# PIC32_BREAKOUT.net
KiCad netlist of a schematic drawn in EAGLE
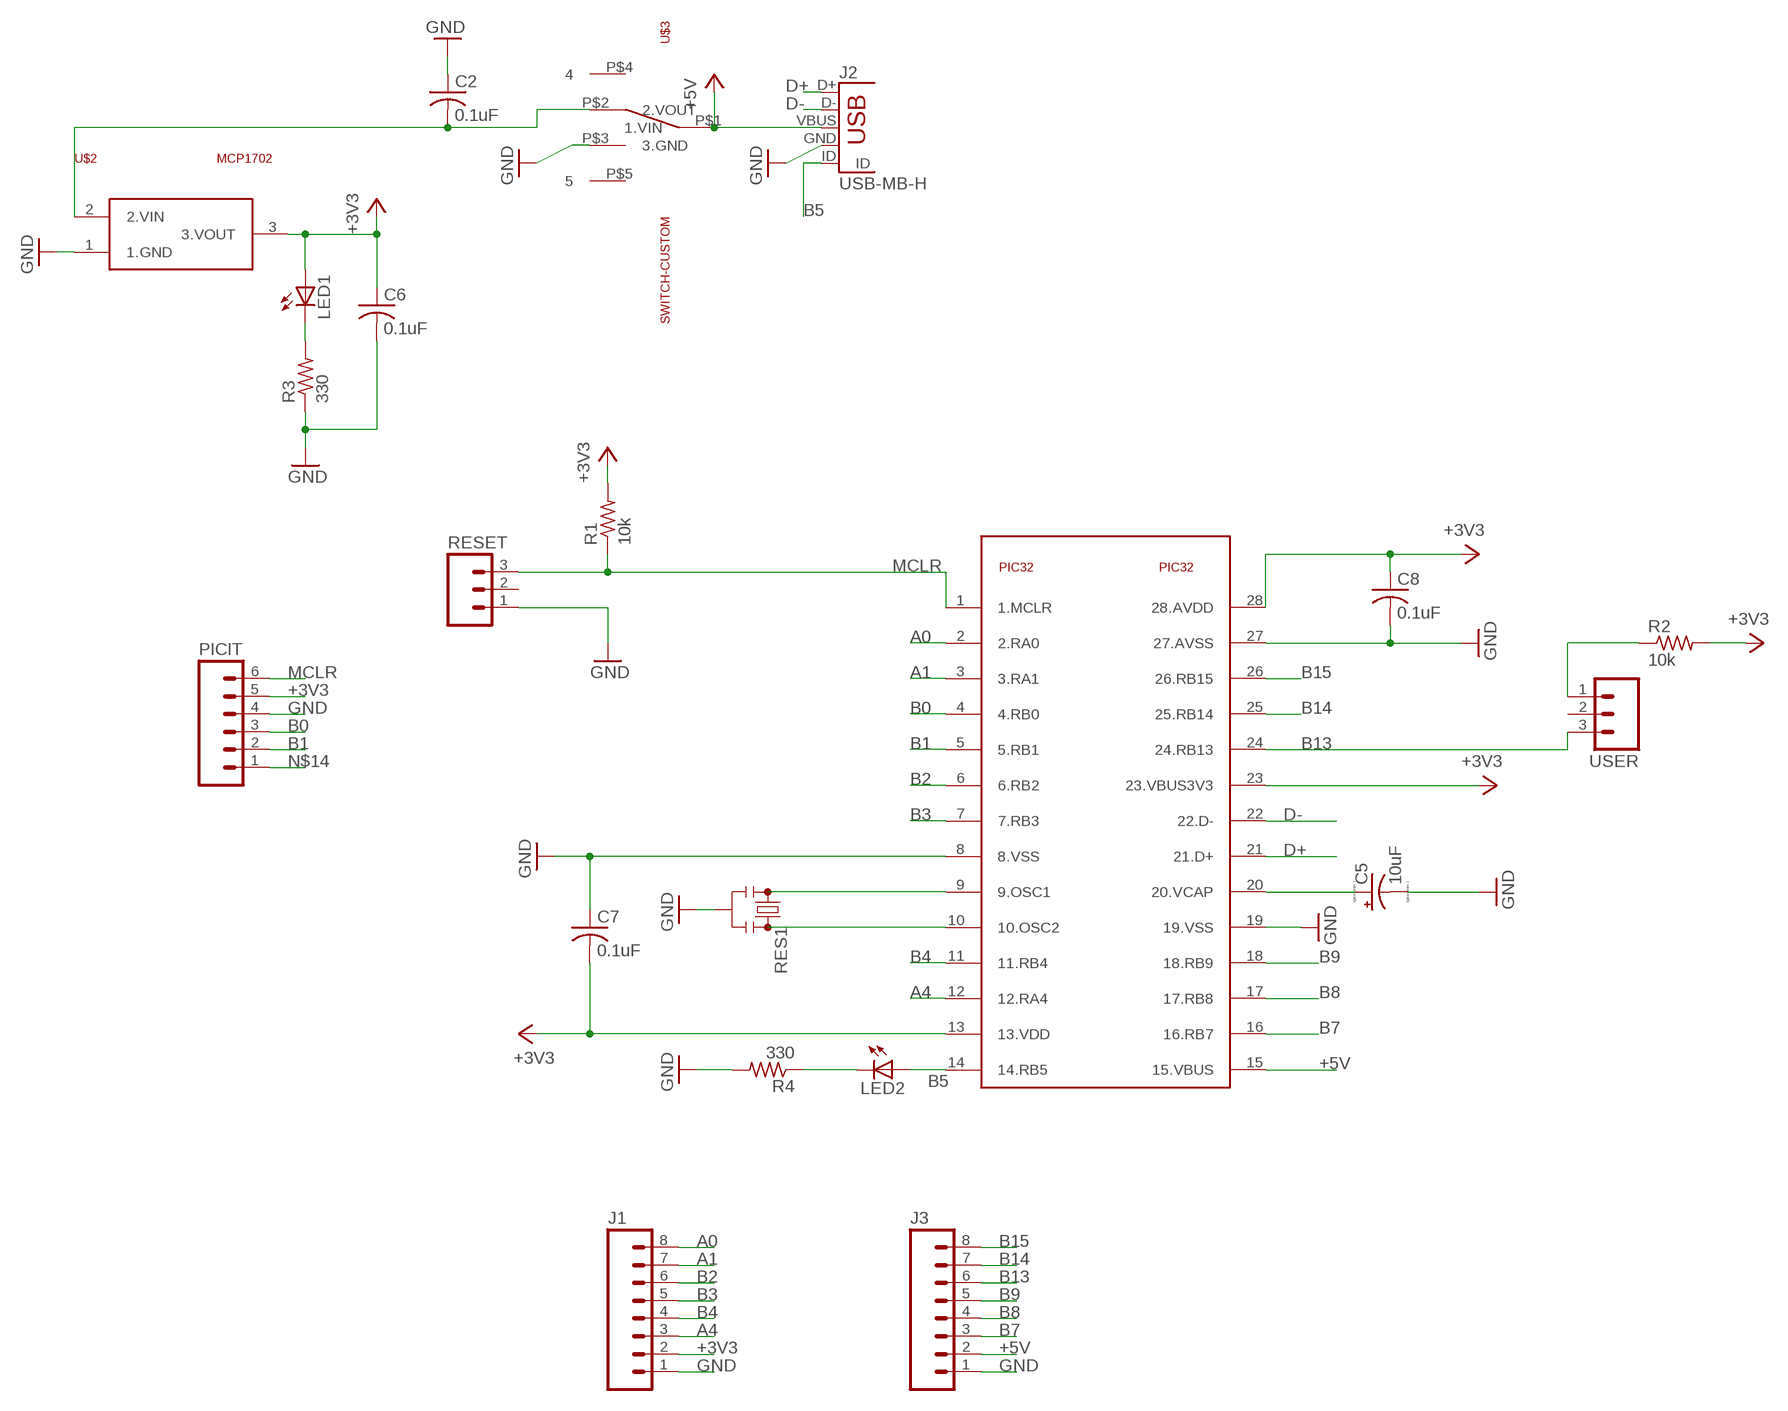
[diagram p0: schematic, sheet 1]

(export (version "E")
  (design (tool "Eeschema 10.0.6"))
  (components
    (comp (ref "C2")
      (value "0.1uF")
      (footprint "eagle-import:C025-024X044")
      (libsource (lib "eagle-import") (part "C-US025-024X044"))
    )
    (comp (ref "C5")
      (value "10uF")
      (footprint "eagle-import:B45181A")
      (libsource (lib "eagle-import") (part "CPOL-USB45181A"))
    )
    (comp (ref "C6")
      (value "0.1uF")
      (footprint "eagle-import:C025-024X044")
      (libsource (lib "eagle-import") (part "C-US025-024X044"))
    )
    (comp (ref "C7")
      (value "0.1uF")
      (footprint "eagle-import:C025-024X044")
      (libsource (lib "eagle-import") (part "C-US025-024X044"))
    )
    (comp (ref "C8")
      (value "0.1uF")
      (footprint "eagle-import:C025-024X044")
      (libsource (lib "eagle-import") (part "C-US025-024X044"))
    )
    (comp (ref "J1")
      (value "M08")
      (footprint "eagle-import:1X08_ROUND")
      (libsource (lib "eagle-import") (part "M08"))
    )
    (comp (ref "J2")
      (value "USB-MB-H")
      (footprint "eagle-import:USB-MB-H")
      (libsource (lib "eagle-import") (part "USB-MB-H"))
    )
    (comp (ref "J3")
      (value "M08")
      (footprint "eagle-import:1X08_ROUND")
      (libsource (lib "eagle-import") (part "M08"))
    )
    (comp (ref "LED1")
      (value "LED3MM")
      (footprint "eagle-import:LED3MM")
      (libsource (lib "eagle-import") (part "LED3MM"))
    )
    (comp (ref "LED2")
      (value "LED3MM")
      (footprint "eagle-import:LED3MM")
      (libsource (lib "eagle-import") (part "LED3MM"))
    )
    (comp (ref "PIC32")
      (value "PIC32")
      (footprint "eagle-import:DIL28-3")
      (libsource (lib "eagle-import") (part "PIC32"))
    )
    (comp (ref "PICIT")
      (value "M06SILK_FEMALE_PTH")
      (footprint "eagle-import:1X06")
      (libsource (lib "eagle-import") (part "M06SILK_FEMALE_PTH"))
    )
    (comp (ref "R1")
      (value "10k")
      (footprint "eagle-import:0204_7")
      (libsource (lib "eagle-import") (part "R-US_0204/7"))
    )
    (comp (ref "R2")
      (value "10k")
      (footprint "eagle-import:0204_7")
      (libsource (lib "eagle-import") (part "R-US_0204/7"))
    )
    (comp (ref "R3")
      (value "330")
      (footprint "eagle-import:0204_7")
      (libsource (lib "eagle-import") (part "R-US_0204/7"))
    )
    (comp (ref "R4")
      (value "330")
      (footprint "eagle-import:0204_7")
      (libsource (lib "eagle-import") (part "R-US_0204/7"))
    )
    (comp (ref "RES1")
      (value "RESONATORPTH")
      (footprint "eagle-import:RESONATOR-PTH")
      (libsource (lib "eagle-import") (part "RESONATORPTH"))
    )
    (comp (ref "RESET")
      (value "M03LOCK")
      (footprint "eagle-import:1X03_LOCK")
      (libsource (lib "eagle-import") (part "M03LOCK"))
    )
    (comp (ref "U$2")
      (value "MCP1702")
      (footprint "eagle-import:TO92")
      (libsource (lib "eagle-import") (part "MCP1702"))
    )
    (comp (ref "U$3")
      (value "SWITCH-CUSTOM")
      (footprint "eagle-import:SWITCH-CUS-H1")
      (libsource (lib "eagle-import") (part "SWITCH-CUSTOM"))
    )
    (comp (ref "USER")
      (value "M03LOCK")
      (footprint "eagle-import:1X03_LOCK")
      (libsource (lib "eagle-import") (part "M03LOCK"))
    )
  )
  (nets
    (net (code "1") (name "+3V3") (class "Default")
      (node (ref "C6") (pin "1") (pinfunction "1_1") (pintype "passive"))
      (node (ref "C7") (pin "2") (pinfunction "2_2") (pintype "passive"))
      (node (ref "C8") (pin "1") (pinfunction "1_1") (pintype "passive"))
      (node (ref "J1") (pin "2") (pinfunction "2_2") (pintype "passive"))
      (node (ref "LED1") (pin "A") (pinfunction "A_A") (pintype "passive"))
      (node (ref "PIC32") (pin "13") (pinfunction "13.VDD_13") (pintype "bidirectional"))
      (node (ref "PIC32") (pin "23") (pinfunction "23.VBUS3V3_23") (pintype "bidirectional"))
      (node (ref "PIC32") (pin "28") (pinfunction "28.AVDD_28") (pintype "bidirectional"))
      (node (ref "PICIT") (pin "5") (pinfunction "5_5") (pintype "passive"))
      (node (ref "R1") (pin "2") (pinfunction "2_2") (pintype "passive"))
      (node (ref "R2") (pin "2") (pinfunction "2_2") (pintype "passive"))
      (node (ref "U$2") (pin "3") (pinfunction "3.VOUT_3") (pintype "bidirectional"))
    )
    (net (code "2") (name "+5V") (class "Default")
      (node (ref "J2") (pin "VBUS") (pinfunction "VBUS_VBUS") (pintype "bidirectional"))
      (node (ref "J3") (pin "2") (pinfunction "2_2") (pintype "passive"))
      (node (ref "PIC32") (pin "15") (pinfunction "15.VBUS_15") (pintype "bidirectional"))
      (node (ref "U$3") (pin "P$1") (pinfunction "1.VIN_P$1") (pintype "bidirectional"))
    )
    (net (code "3") (name "/A0") (class "Default")
      (node (ref "J1") (pin "8") (pinfunction "8_8") (pintype "passive"))
      (node (ref "PIC32") (pin "2") (pinfunction "2.RA0_2") (pintype "bidirectional"))
    )
    (net (code "4") (name "/A1") (class "Default")
      (node (ref "J1") (pin "7") (pinfunction "7_7") (pintype "passive"))
      (node (ref "PIC32") (pin "3") (pinfunction "3.RA1_3") (pintype "bidirectional"))
    )
    (net (code "5") (name "/A4") (class "Default")
      (node (ref "J1") (pin "3") (pinfunction "3_3") (pintype "passive"))
      (node (ref "PIC32") (pin "12") (pinfunction "12.RA4_12") (pintype "bidirectional"))
    )
    (net (code "6") (name "/B0") (class "Default")
      (node (ref "PIC32") (pin "4") (pinfunction "4.RB0_4") (pintype "bidirectional"))
      (node (ref "PICIT") (pin "3") (pinfunction "3_3") (pintype "passive"))
    )
    (net (code "7") (name "/B1") (class "Default")
      (node (ref "PIC32") (pin "5") (pinfunction "5.RB1_5") (pintype "bidirectional"))
      (node (ref "PICIT") (pin "2") (pinfunction "2_2") (pintype "passive"))
    )
    (net (code "8") (name "/B2") (class "Default")
      (node (ref "J1") (pin "6") (pinfunction "6_6") (pintype "passive"))
      (node (ref "PIC32") (pin "6") (pinfunction "6.RB2_6") (pintype "bidirectional"))
    )
    (net (code "9") (name "/B3") (class "Default")
      (node (ref "J1") (pin "5") (pinfunction "5_5") (pintype "passive"))
      (node (ref "PIC32") (pin "7") (pinfunction "7.RB3_7") (pintype "bidirectional"))
    )
    (net (code "10") (name "/B4") (class "Default")
      (node (ref "J1") (pin "4") (pinfunction "4_4") (pintype "passive"))
      (node (ref "PIC32") (pin "11") (pinfunction "11.RB4_11") (pintype "bidirectional"))
    )
    (net (code "11") (name "/B5") (class "Default")
      (node (ref "J2") (pin "ID") (pinfunction "ID_ID") (pintype "bidirectional"))
      (node (ref "LED2") (pin "A") (pinfunction "A_A") (pintype "passive"))
      (node (ref "PIC32") (pin "14") (pinfunction "14.RB5_14") (pintype "bidirectional"))
    )
    (net (code "12") (name "/B7") (class "Default")
      (node (ref "J3") (pin "3") (pinfunction "3_3") (pintype "passive"))
      (node (ref "PIC32") (pin "16") (pinfunction "16.RB7_16") (pintype "bidirectional"))
    )
    (net (code "13") (name "/B8") (class "Default")
      (node (ref "J3") (pin "4") (pinfunction "4_4") (pintype "passive"))
      (node (ref "PIC32") (pin "17") (pinfunction "17.RB8_17") (pintype "bidirectional"))
    )
    (net (code "14") (name "/B9") (class "Default")
      (node (ref "J3") (pin "5") (pinfunction "5_5") (pintype "passive"))
      (node (ref "PIC32") (pin "18") (pinfunction "18.RB9_18") (pintype "bidirectional"))
    )
    (net (code "15") (name "/B13") (class "Default")
      (node (ref "J3") (pin "6") (pinfunction "6_6") (pintype "passive"))
      (node (ref "PIC32") (pin "24") (pinfunction "24.RB13_24") (pintype "bidirectional"))
      (node (ref "USER") (pin "3") (pinfunction "3_3") (pintype "passive"))
    )
    (net (code "16") (name "/B14") (class "Default")
      (node (ref "J3") (pin "7") (pinfunction "7_7") (pintype "passive"))
      (node (ref "PIC32") (pin "25") (pinfunction "25.RB14_25") (pintype "bidirectional"))
    )
    (net (code "17") (name "/B15") (class "Default")
      (node (ref "J3") (pin "8") (pinfunction "8_8") (pintype "passive"))
      (node (ref "PIC32") (pin "26") (pinfunction "26.RB15_26") (pintype "bidirectional"))
    )
    (net (code "18") (name "/D+") (class "Default")
      (node (ref "J2") (pin "D+") (pinfunction "D+_D+") (pintype "bidirectional"))
      (node (ref "PIC32") (pin "21") (pinfunction "21.D+_21") (pintype "bidirectional"))
    )
    (net (code "19") (name "/D-") (class "Default")
      (node (ref "J2") (pin "D-") (pinfunction "D-_D-") (pintype "bidirectional"))
      (node (ref "PIC32") (pin "22") (pinfunction "22.D-_22") (pintype "bidirectional"))
    )
    (net (code "20") (name "/MCLR") (class "Default")
      (node (ref "PIC32") (pin "1") (pinfunction "1.MCLR_1") (pintype "bidirectional"))
      (node (ref "PICIT") (pin "6") (pinfunction "6_6") (pintype "passive"))
      (node (ref "R1") (pin "1") (pinfunction "1_1") (pintype "passive"))
      (node (ref "RESET") (pin "3") (pinfunction "3_3") (pintype "passive"))
    )
    (net (code "21") (name "/N$14") (class "Default")
      (node (ref "PICIT") (pin "1") (pinfunction "1_1") (pintype "passive"))
    )
    (net (code "22") (name "GND") (class "Default")
      (node (ref "C2") (pin "1") (pinfunction "1_1") (pintype "passive"))
      (node (ref "C5") (pin "-") (pinfunction "-_-") (pintype "passive"))
      (node (ref "C6") (pin "2") (pinfunction "2_2") (pintype "passive"))
      (node (ref "C7") (pin "1") (pinfunction "1_1") (pintype "passive"))
      (node (ref "C8") (pin "2") (pinfunction "2_2") (pintype "passive"))
      (node (ref "J1") (pin "1") (pinfunction "1_1") (pintype "passive"))
      (node (ref "J2") (pin "GND") (pinfunction "GND_GND") (pintype "bidirectional"))
      (node (ref "J3") (pin "1") (pinfunction "1_1") (pintype "passive"))
      (node (ref "PIC32") (pin "19") (pinfunction "19.VSS_19") (pintype "bidirectional"))
      (node (ref "PIC32") (pin "27") (pinfunction "27.AVSS_27") (pintype "bidirectional"))
      (node (ref "PIC32") (pin "8") (pinfunction "8.VSS_8") (pintype "bidirectional"))
      (node (ref "PICIT") (pin "4") (pinfunction "4_4") (pintype "passive"))
      (node (ref "R3") (pin "1") (pinfunction "1_1") (pintype "passive"))
      (node (ref "R4") (pin "2") (pinfunction "2_2") (pintype "passive"))
      (node (ref "RES1") (pin "2") (pinfunction "2_2") (pintype "passive"))
      (node (ref "RESET") (pin "1") (pinfunction "1_1") (pintype "passive"))
      (node (ref "U$2") (pin "1") (pinfunction "1.GND_1") (pintype "bidirectional"))
      (node (ref "U$3") (pin "P$3") (pinfunction "3.GND_P$3") (pintype "bidirectional"))
    )
    (net (code "23") (name "Net-(LED1-C)") (class "Default")
      (node (ref "LED1") (pin "K") (pinfunction "C_K") (pintype "passive"))
      (node (ref "R3") (pin "2") (pinfunction "2_2") (pintype "passive"))
    )
    (net (code "24") (name "Net-(LED2-C)") (class "Default")
      (node (ref "LED2") (pin "K") (pinfunction "C_K") (pintype "passive"))
      (node (ref "R4") (pin "1") (pinfunction "1_1") (pintype "passive"))
    )
    (net (code "25") (name "Net-(PIC32-9.OSC1)") (class "Default")
      (node (ref "PIC32") (pin "9") (pinfunction "9.OSC1_9") (pintype "bidirectional"))
      (node (ref "RES1") (pin "1") (pinfunction "1_1") (pintype "passive"))
    )
    (net (code "26") (name "Net-(PIC32-10.OSC2)") (class "Default")
      (node (ref "PIC32") (pin "10") (pinfunction "10.OSC2_10") (pintype "bidirectional"))
      (node (ref "RES1") (pin "3") (pinfunction "3_3") (pintype "passive"))
    )
    (net (code "27") (name "Net-(PIC32-20.VCAP)") (class "Default")
      (node (ref "C5") (pin "+") (pinfunction "+_+") (pintype "passive"))
      (node (ref "PIC32") (pin "20") (pinfunction "20.VCAP_20") (pintype "bidirectional"))
    )
    (net (code "28") (name "Net-(R2-Pad1)") (class "Default")
      (node (ref "R2") (pin "1") (pinfunction "1_1") (pintype "passive"))
      (node (ref "USER") (pin "1") (pinfunction "1_1") (pintype "passive"))
    )
    (net (code "29") (name "Net-(U$2-2.VIN)") (class "Default")
      (node (ref "C2") (pin "2") (pinfunction "2_2") (pintype "passive"))
      (node (ref "U$2") (pin "2") (pinfunction "2.VIN_2") (pintype "bidirectional"))
      (node (ref "U$3") (pin "P$2") (pinfunction "2.VOUT_P$2") (pintype "bidirectional"))
    )
    (net (code "30") (name "unconnected-(RESET-Pad2)") (class "Default")
      (node (ref "RESET") (pin "2") (pinfunction "2_2") (pintype "passive"))
    )
    (net (code "31") (name "unconnected-(U$3-4-PadP$4)") (class "Default")
      (node (ref "U$3") (pin "P$4") (pinfunction "4_P$4") (pintype "bidirectional"))
    )
    (net (code "32") (name "unconnected-(U$3-5-PadP$5)") (class "Default")
      (node (ref "U$3") (pin "P$5") (pinfunction "5_P$5") (pintype "bidirectional"))
    )
    (net (code "33") (name "unconnected-(USER-Pad2)") (class "Default")
      (node (ref "USER") (pin "2") (pinfunction "2_2") (pintype "passive"))
    )
  )
)
